# netflix-switch.net
KiCad netlist of a schematic drawn in EAGLE
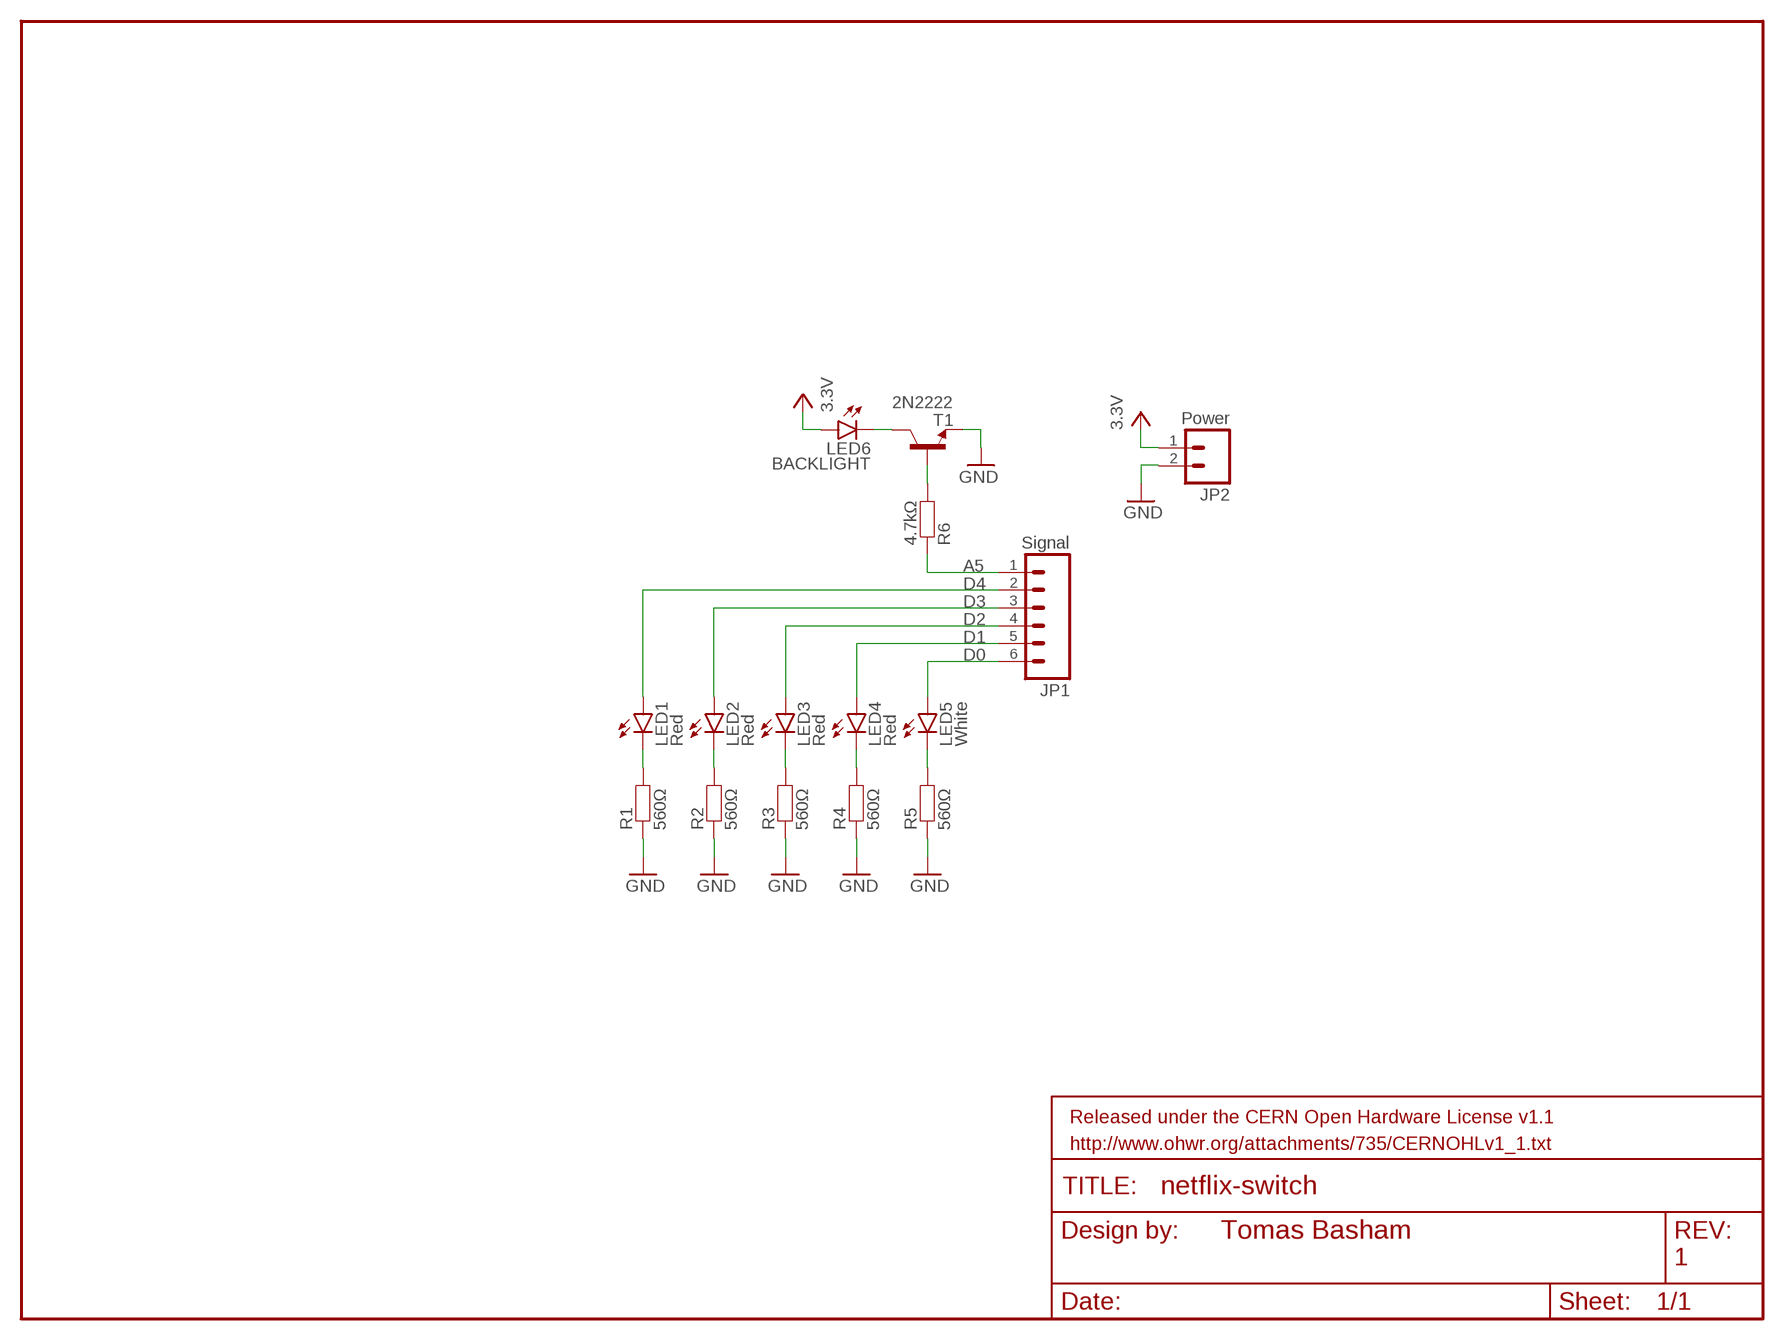
[diagram p0: schematic, sheet 1]

(export (version "E")
  (design (tool "Eeschema 10.0.6"))
  (components
    (comp (ref "FRAME1")
      (value "FRAME-LETTER")
      (footprint "eagle-import:CREATIVE_COMMONS")
      (fields (field (name "OC_FARNELL") "unknown"))
      (libsource (lib "eagle-import") (part "FRAME-LETTER"))
    )
    (comp (ref "JP1")
      (value "Signal")
      (footprint "eagle-import:1X06")
      (libsource (lib "eagle-import") (part "M06SIP"))
    )
    (comp (ref "JP2")
      (value "Power")
      (footprint "eagle-import:1X02")
      (libsource (lib "eagle-import") (part "M02PTH"))
    )
    (comp (ref "LED1")
      (value "Red")
      (footprint "eagle-import:LED3MM-NS")
      (fields (field (name "MF") "KINGBRIGHT") (field (name "MPN") "L-934ID-5V"))
      (libsource (lib "eagle-import") (part "LED-3MM-NO_SILK"))
    )
    (comp (ref "LED2")
      (value "Red")
      (footprint "eagle-import:LED3MM-NS")
      (fields (field (name "MF") "KINGBRIGHT") (field (name "MPN") "L-934ID-5V"))
      (libsource (lib "eagle-import") (part "LED-3MM-NO_SILK"))
    )
    (comp (ref "LED3")
      (value "Red")
      (footprint "eagle-import:LED3MM-NS")
      (fields (field (name "MF") "KINGBRIGHT") (field (name "MPN") "L-934ID-5V"))
      (libsource (lib "eagle-import") (part "LED-3MM-NO_SILK"))
    )
    (comp (ref "LED4")
      (value "Red")
      (footprint "eagle-import:LED3MM-NS")
      (fields (field (name "MF") "KINGBRIGHT") (field (name "MPN") "L-934ID-5V"))
      (libsource (lib "eagle-import") (part "LED-3MM-NO_SILK"))
    )
    (comp (ref "LED5")
      (value "White")
      (footprint "eagle-import:LED3MM-NS")
      (fields (field (name "MF") "VISHAY") (field (name "MPN") "VLHW4100"))
      (libsource (lib "eagle-import") (part "LED-3MM-NO_SILK"))
    )
    (comp (ref "LED6")
      (value "BACKLIGHT")
      (footprint "eagle-import:LED5MM-NS")
      (libsource (lib "eagle-import") (part "LED-5MM-NO_SILK"))
    )
    (comp (ref "R1")
      (value "560Ω")
      (footprint "eagle-import:0603")
      (fields (field (name "MF") "VISHAY") (field (name "MPN") "CRCW0603560RFKEA"))
      (libsource (lib "eagle-import") (part "RESISTOR0603"))
    )
    (comp (ref "R2")
      (value "560Ω")
      (footprint "eagle-import:0603")
      (fields (field (name "MF") "VISHAY") (field (name "MPN") "CRCW0603560RFKEA"))
      (libsource (lib "eagle-import") (part "RESISTOR0603"))
    )
    (comp (ref "R3")
      (value "560Ω")
      (footprint "eagle-import:0603")
      (fields (field (name "MF") "VISHAY") (field (name "MPN") "CRCW0603560RFKEA"))
      (libsource (lib "eagle-import") (part "RESISTOR0603"))
    )
    (comp (ref "R4")
      (value "560Ω")
      (footprint "eagle-import:0603")
      (fields (field (name "MF") "VISHAY") (field (name "MPN") "CRCW0603560RFKEA"))
      (libsource (lib "eagle-import") (part "RESISTOR0603"))
    )
    (comp (ref "R5")
      (value "560Ω")
      (footprint "eagle-import:0603")
      (fields (field (name "MF") "VISHAY") (field (name "MPN") "CRCW0603560RFKEA"))
      (libsource (lib "eagle-import") (part "RESISTOR0603"))
    )
    (comp (ref "R6")
      (value "4.7kΩ")
      (footprint "eagle-import:0603")
      (fields (field (name "MF") "VISHAY") (field (name "MPN") "CRCW06034K70FKEA"))
      (libsource (lib "eagle-import") (part "RESISTOR0603"))
    )
    (comp (ref "T1")
      (value "2N2222")
      (footprint "eagle-import:TO92-EBC-OVAL")
      (fields (field (name "MF") "ON SEMICONDUCTOR") (field (name "MPN") "P2N2222AG"))
      (libsource (lib "eagle-import") (part "2N2222"))
    )
  )
  (nets
    (net (code "1") (name "/A5") (class "Default")
      (node (ref "JP1") (pin "1") (pinfunction "1_1") (pintype "passive"))
      (node (ref "R6") (pin "1") (pinfunction "1_1") (pintype "passive"))
    )
    (net (code "2") (name "/D0") (class "Default")
      (node (ref "JP1") (pin "6") (pinfunction "6_6") (pintype "passive"))
      (node (ref "LED5") (pin "A") (pinfunction "A_A") (pintype "passive"))
    )
    (net (code "3") (name "/D1") (class "Default")
      (node (ref "JP1") (pin "5") (pinfunction "5_5") (pintype "passive"))
      (node (ref "LED4") (pin "A") (pinfunction "A_A") (pintype "passive"))
    )
    (net (code "4") (name "/D2") (class "Default")
      (node (ref "JP1") (pin "4") (pinfunction "4_4") (pintype "passive"))
      (node (ref "LED3") (pin "A") (pinfunction "A_A") (pintype "passive"))
    )
    (net (code "5") (name "/D3") (class "Default")
      (node (ref "JP1") (pin "3") (pinfunction "3_3") (pintype "passive"))
      (node (ref "LED2") (pin "A") (pinfunction "A_A") (pintype "passive"))
    )
    (net (code "6") (name "/D4") (class "Default")
      (node (ref "JP1") (pin "2") (pinfunction "2_2") (pintype "passive"))
      (node (ref "LED1") (pin "A") (pinfunction "A_A") (pintype "passive"))
    )
    (net (code "7") (name "3.3V") (class "Default")
      (node (ref "JP2") (pin "1") (pinfunction "1_1") (pintype "passive"))
      (node (ref "LED6") (pin "A") (pinfunction "A_A") (pintype "passive"))
    )
    (net (code "8") (name "GND") (class "Default")
      (node (ref "JP2") (pin "2") (pinfunction "2_2") (pintype "passive"))
      (node (ref "R1") (pin "1") (pinfunction "1_1") (pintype "passive"))
      (node (ref "R2") (pin "1") (pinfunction "1_1") (pintype "passive"))
      (node (ref "R3") (pin "1") (pinfunction "1_1") (pintype "passive"))
      (node (ref "R4") (pin "1") (pinfunction "1_1") (pintype "passive"))
      (node (ref "R5") (pin "1") (pinfunction "1_1") (pintype "passive"))
      (node (ref "T1") (pin "E") (pinfunction "E_E") (pintype "passive"))
    )
    (net (code "9") (name "Net-(LED1-C)") (class "Default")
      (node (ref "LED1") (pin "K") (pinfunction "C_K") (pintype "passive"))
      (node (ref "R1") (pin "2") (pinfunction "2_2") (pintype "passive"))
    )
    (net (code "10") (name "Net-(LED2-C)") (class "Default")
      (node (ref "LED2") (pin "K") (pinfunction "C_K") (pintype "passive"))
      (node (ref "R2") (pin "2") (pinfunction "2_2") (pintype "passive"))
    )
    (net (code "11") (name "Net-(LED3-C)") (class "Default")
      (node (ref "LED3") (pin "K") (pinfunction "C_K") (pintype "passive"))
      (node (ref "R3") (pin "2") (pinfunction "2_2") (pintype "passive"))
    )
    (net (code "12") (name "Net-(LED4-C)") (class "Default")
      (node (ref "LED4") (pin "K") (pinfunction "C_K") (pintype "passive"))
      (node (ref "R4") (pin "2") (pinfunction "2_2") (pintype "passive"))
    )
    (net (code "13") (name "Net-(LED5-C)") (class "Default")
      (node (ref "LED5") (pin "K") (pinfunction "C_K") (pintype "passive"))
      (node (ref "R5") (pin "2") (pinfunction "2_2") (pintype "passive"))
    )
    (net (code "14") (name "Net-(LED6-C)") (class "Default")
      (node (ref "LED6") (pin "K") (pinfunction "C_K") (pintype "passive"))
      (node (ref "T1") (pin "C") (pinfunction "C_C") (pintype "passive"))
    )
    (net (code "15") (name "Net-(R6-Pad2)") (class "Default")
      (node (ref "R6") (pin "2") (pinfunction "2_2") (pintype "passive"))
      (node (ref "T1") (pin "B") (pinfunction "B_B") (pintype "passive"))
    )
  )
)
